# displacement_sensor.net
KiCad netlist of a schematic drawn in EAGLE
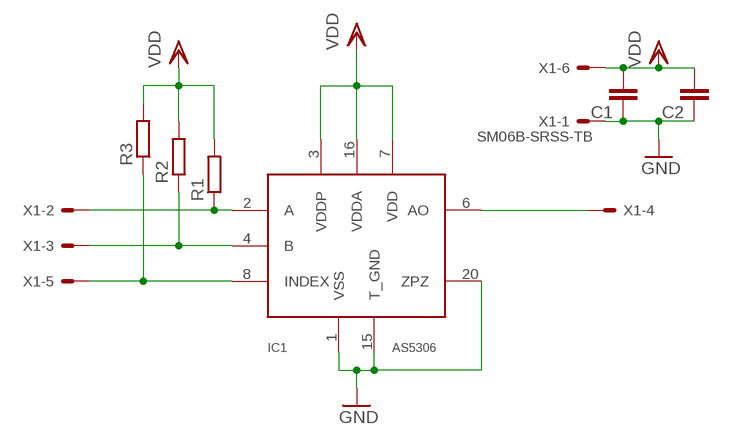
[diagram p0: schematic, sheet 1]

(export (version "E")
  (design (tool "Eeschema 10.0.6"))
  (components
    (comp (ref "C1")
      (value "C-EUC0402K")
      (footprint "eagle-import:C0402K")
      (libsource (lib "eagle-import") (part "C-EUC0402K"))
    )
    (comp (ref "C2")
      (value "C-EUC0402K")
      (footprint "eagle-import:C0402K")
      (libsource (lib "eagle-import") (part "C-EUC0402K"))
    )
    (comp (ref "IC1")
      (value "AS5306")
      (footprint "eagle-import:TSSOP20")
      (libsource (lib "eagle-import") (part "AS5306"))
    )
    (comp (ref "R1")
      (value "R-EU_R0402")
      (footprint "eagle-import:R0402")
      (libsource (lib "eagle-import") (part "R-EU_R0402"))
    )
    (comp (ref "R2")
      (value "R-EU_R0402")
      (footprint "eagle-import:R0402")
      (libsource (lib "eagle-import") (part "R-EU_R0402"))
    )
    (comp (ref "R3")
      (value "R-EU_R0402")
      (footprint "eagle-import:R0402")
      (libsource (lib "eagle-import") (part "R-EU_R0402"))
    )
    (comp (ref "X1")
      (value "SM06B-SRSS-TB")
      (footprint "eagle-import:SM06B-SRSS-TB")
      (libsource (lib "eagle-import") (part "?M06B-SRSS-TBS"))
    )
  )
  (nets
    (net (code "1") (name "GND") (class "Default")
      (node (ref "C1") (pin "1") (pinfunction "1_1") (pintype "passive"))
      (node (ref "C2") (pin "1") (pinfunction "1_1") (pintype "passive"))
      (node (ref "IC1") (pin "1") (pinfunction "VSS_1") (pintype "bidirectional"))
      (node (ref "IC1") (pin "15") (pinfunction "T_GND_15") (pintype "bidirectional"))
      (node (ref "IC1") (pin "20") (pinfunction "ZPZ_20") (pintype "bidirectional"))
      (node (ref "X1") (pin "1") (pinfunction "S_1") (pintype "passive"))
    )
    (net (code "2") (name "Net-(IC1-A)") (class "Default")
      (node (ref "IC1") (pin "2") (pinfunction "A_2") (pintype "bidirectional"))
      (node (ref "R1") (pin "1") (pinfunction "1_1") (pintype "passive"))
      (node (ref "X1") (pin "2") (pinfunction "S_2") (pintype "passive"))
    )
    (net (code "3") (name "Net-(IC1-AO)") (class "Default")
      (node (ref "IC1") (pin "6") (pinfunction "AO_6") (pintype "bidirectional"))
      (node (ref "X1") (pin "4") (pinfunction "S_4") (pintype "passive"))
    )
    (net (code "4") (name "Net-(IC1-B)") (class "Default")
      (node (ref "IC1") (pin "4") (pinfunction "B_4") (pintype "bidirectional"))
      (node (ref "R2") (pin "1") (pinfunction "1_1") (pintype "passive"))
      (node (ref "X1") (pin "3") (pinfunction "S_3") (pintype "passive"))
    )
    (net (code "5") (name "Net-(IC1-INDEX)") (class "Default")
      (node (ref "IC1") (pin "8") (pinfunction "INDEX_8") (pintype "bidirectional"))
      (node (ref "R3") (pin "1") (pinfunction "1_1") (pintype "passive"))
      (node (ref "X1") (pin "5") (pinfunction "S_5") (pintype "passive"))
    )
    (net (code "6") (name "VDD") (class "Default")
      (node (ref "C1") (pin "2") (pinfunction "2_2") (pintype "passive"))
      (node (ref "C2") (pin "2") (pinfunction "2_2") (pintype "passive"))
      (node (ref "IC1") (pin "16") (pinfunction "VDDA_16") (pintype "bidirectional"))
      (node (ref "IC1") (pin "3") (pinfunction "VDDP_3") (pintype "bidirectional"))
      (node (ref "IC1") (pin "7") (pinfunction "VDD_7") (pintype "bidirectional"))
      (node (ref "R1") (pin "2") (pinfunction "2_2") (pintype "passive"))
      (node (ref "R2") (pin "2") (pinfunction "2_2") (pintype "passive"))
      (node (ref "R3") (pin "2") (pinfunction "2_2") (pintype "passive"))
      (node (ref "X1") (pin "6") (pinfunction "S_6") (pintype "passive"))
    )
  )
)
